# resonatev2.net
KiCad netlist of a schematic drawn in EAGLE
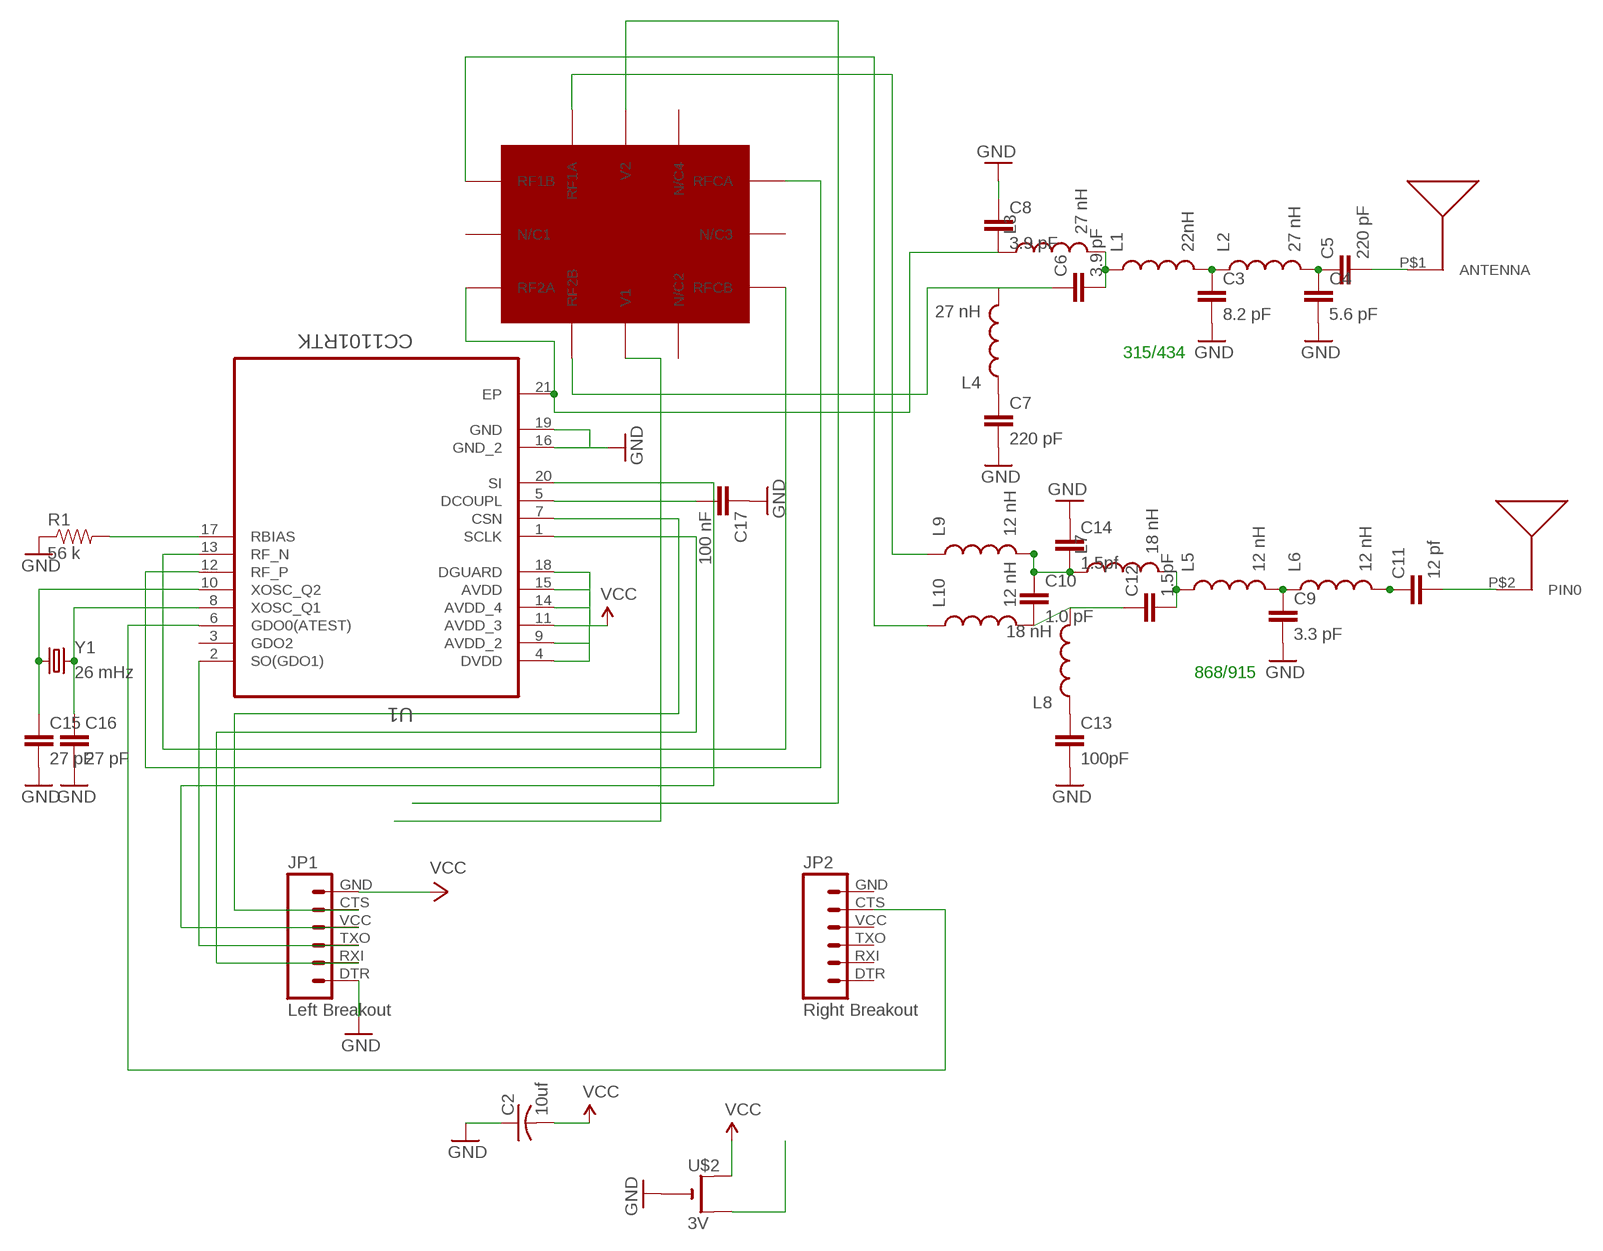
[diagram p0: schematic, sheet 1]

(export (version "E")
  (design (tool "Eeschema 10.0.6"))
  (components
    (comp (ref "C2")
      (value "10uf")
      (footprint "eagle-import:C0603")
      (libsource (lib "eagle-import") (part "C-USC0603"))
    )
    (comp (ref "C3")
      (value "8.2 pF")
      (footprint "eagle-import:0402-CAP")
      (libsource (lib "eagle-import") (part "CAP0402-CAP"))
    )
    (comp (ref "C4")
      (value "5.6 pF")
      (footprint "eagle-import:0402-CAP")
      (libsource (lib "eagle-import") (part "CAP0402-CAP"))
    )
    (comp (ref "C5")
      (value "220 pF")
      (footprint "eagle-import:0402-CAP")
      (libsource (lib "eagle-import") (part "CAP0402-CAP"))
    )
    (comp (ref "C6")
      (value "3.9 pF")
      (footprint "eagle-import:0402-CAP")
      (libsource (lib "eagle-import") (part "CAP0402-CAP"))
    )
    (comp (ref "C7")
      (value "220 pF")
      (footprint "eagle-import:0402-CAP")
      (libsource (lib "eagle-import") (part "CAP0402-CAP"))
    )
    (comp (ref "C8")
      (value "3.9 pF")
      (footprint "eagle-import:0402-CAP")
      (libsource (lib "eagle-import") (part "CAP0402-CAP"))
    )
    (comp (ref "C9")
      (value "3.3 pF")
      (footprint "eagle-import:0402-CAP")
      (libsource (lib "eagle-import") (part "CAP0402-CAP"))
    )
    (comp (ref "C10")
      (value "1.0 pF")
      (footprint "eagle-import:0402-CAP")
      (libsource (lib "eagle-import") (part "CAP0402-CAP"))
    )
    (comp (ref "C11")
      (value "12 pf")
      (footprint "eagle-import:0402-CAP")
      (libsource (lib "eagle-import") (part "CAP0402-CAP"))
    )
    (comp (ref "C12")
      (value "1.5pF")
      (footprint "eagle-import:0402-CAP")
      (libsource (lib "eagle-import") (part "CAP0402-CAP"))
    )
    (comp (ref "C13")
      (value "100pF")
      (footprint "eagle-import:0402-CAP")
      (libsource (lib "eagle-import") (part "CAP0402-CAP"))
    )
    (comp (ref "C14")
      (value "1.5pf")
      (footprint "eagle-import:0402-CAP")
      (libsource (lib "eagle-import") (part "CAP0402-CAP"))
    )
    (comp (ref "C15")
      (value "27 pF")
      (footprint "eagle-import:0402-CAP")
      (libsource (lib "eagle-import") (part "CAP0402-CAP"))
    )
    (comp (ref "C16")
      (value "27 pF")
      (footprint "eagle-import:0402-CAP")
      (libsource (lib "eagle-import") (part "CAP0402-CAP"))
    )
    (comp (ref "C17")
      (value "100 nF")
      (footprint "eagle-import:0402-CAP")
      (libsource (lib "eagle-import") (part "CAP0402-CAP"))
    )
    (comp (ref "JP1")
      (value "Left Breakout")
      (footprint "eagle-import:1X06")
      (libsource (lib "eagle-import") (part "M06SIP"))
    )
    (comp (ref "JP2")
      (value "Right Breakout")
      (footprint "eagle-import:1X06")
      (libsource (lib "eagle-import") (part "M06SIP"))
    )
    (comp (ref "L1")
      (value "22nH")
      (footprint "eagle-import:C0402")
      (libsource (lib "eagle-import") (part "INDUCTOR0402"))
    )
    (comp (ref "L2")
      (value "27 nH")
      (footprint "eagle-import:C0402")
      (libsource (lib "eagle-import") (part "INDUCTOR0402"))
    )
    (comp (ref "L3")
      (value "27 nH")
      (footprint "eagle-import:C0402")
      (libsource (lib "eagle-import") (part "INDUCTOR0402"))
    )
    (comp (ref "L4")
      (value "27 nH")
      (footprint "eagle-import:C0402")
      (libsource (lib "eagle-import") (part "INDUCTOR0402"))
    )
    (comp (ref "L5")
      (value "12 nH")
      (footprint "eagle-import:C0402")
      (libsource (lib "eagle-import") (part "INDUCTOR0402"))
    )
    (comp (ref "L6")
      (value "12 nH")
      (footprint "eagle-import:C0402")
      (libsource (lib "eagle-import") (part "INDUCTOR0402"))
    )
    (comp (ref "L7")
      (value "18 nH")
      (footprint "eagle-import:C0402")
      (libsource (lib "eagle-import") (part "INDUCTOR0402"))
    )
    (comp (ref "L8")
      (value "18 nH")
      (footprint "eagle-import:C0402")
      (libsource (lib "eagle-import") (part "INDUCTOR0402"))
    )
    (comp (ref "L9")
      (value "12 nH")
      (footprint "eagle-import:C0402")
      (libsource (lib "eagle-import") (part "INDUCTOR0402"))
    )
    (comp (ref "L10")
      (value "12 nH")
      (footprint "eagle-import:C0402")
      (libsource (lib "eagle-import") (part "INDUCTOR0402"))
    )
    (comp (ref "R1")
      (value "56 k")
      (footprint "eagle-import:0603-RES")
      (libsource (lib "eagle-import") (part "RESISTOR0603-RES"))
    )
    (comp (ref "U$2")
      (value "3V")
      (footprint "eagle-import:CR2032-THRU")
      (libsource (lib "eagle-import") (part "CR2032THM"))
    )
    (comp (ref "U$3")
      (value "ANT-868-JJB-ST")
      (footprint "eagle-import:ANT-868-JJB-ST")
      (libsource (lib "eagle-import") (part "ANT-868-JJB-ST"))
    )
    (comp (ref "U$5")
      (value "SKY13354-368LF")
      (footprint "eagle-import:SKY13354-368LF")
      (libsource (lib "eagle-import") (part "SKY13354-368LF"))
    )
    (comp (ref "U$6")
      (value "ANT1204F002R0433A")
      (footprint "eagle-import:ANT1204F002R0433A")
      (libsource (lib "eagle-import") (part "ANT1204F002R0433A"))
    )
    (comp (ref "U1")
      (value "CC1101RTK")
      (footprint "eagle-import:QFN50P400X400X90-21N")
      (libsource (lib "eagle-import") (part "CC1101RTK"))
    )
    (comp (ref "Y1")
      (value "26 mHz")
      (footprint "eagle-import:CRYSTAL-SMD-5X3")
      (libsource (lib "eagle-import") (part "CRYSTAL5X3"))
    )
  )
  (nets
    (net (code "1") (name "GND") (class "Default")
      (node (ref "C13") (pin "2") (pinfunction "2_2") (pintype "passive"))
      (node (ref "C14") (pin "1") (pinfunction "1_1") (pintype "passive"))
      (node (ref "C15") (pin "2") (pinfunction "2_2") (pintype "passive"))
      (node (ref "C16") (pin "2") (pinfunction "2_2") (pintype "passive"))
      (node (ref "C17") (pin "1") (pinfunction "1_1") (pintype "passive"))
      (node (ref "C2") (pin "1") (pinfunction "1_1") (pintype "passive"))
      (node (ref "C3") (pin "2") (pinfunction "2_2") (pintype "passive"))
      (node (ref "C4") (pin "2") (pinfunction "2_2") (pintype "passive"))
      (node (ref "C7") (pin "2") (pinfunction "2_2") (pintype "passive"))
      (node (ref "C8") (pin "1") (pinfunction "1_1") (pintype "passive"))
      (node (ref "C9") (pin "2") (pinfunction "2_2") (pintype "passive"))
      (node (ref "JP1") (pin "DTR") (pinfunction "1_DTR") (pintype "passive"))
      (node (ref "R1") (pin "1") (pinfunction "1_1") (pintype "passive"))
      (node (ref "U$2") (pin "-") (pinfunction "-_-") (pintype "passive"))
      (node (ref "U1") (pin "16") (pinfunction "GND_2_16") (pintype "passive"))
      (node (ref "U1") (pin "19") (pinfunction "GND_19") (pintype "passive"))
    )
    (net (code "2") (name "Net-(C3-Pad1)") (class "Default")
      (node (ref "C3") (pin "1") (pinfunction "1_1") (pintype "passive"))
      (node (ref "L1") (pin "2") (pinfunction "2_2") (pintype "passive"))
      (node (ref "L2") (pin "1") (pinfunction "1_1") (pintype "passive"))
    )
    (net (code "3") (name "Net-(C4-Pad1)") (class "Default")
      (node (ref "C4") (pin "1") (pinfunction "1_1") (pintype "passive"))
      (node (ref "C5") (pin "1") (pinfunction "1_1") (pintype "passive"))
      (node (ref "L2") (pin "2") (pinfunction "2_2") (pintype "passive"))
    )
    (net (code "4") (name "Net-(C6-Pad1)") (class "Default")
      (node (ref "C6") (pin "1") (pinfunction "1_1") (pintype "passive"))
      (node (ref "L4") (pin "2") (pinfunction "2_2") (pintype "passive"))
      (node (ref "U$5") (pin "RF2B") (pinfunction "RF2B_RF2B") (pintype "bidirectional"))
    )
    (net (code "5") (name "Net-(C6-Pad2)") (class "Default")
      (node (ref "C6") (pin "2") (pinfunction "2_2") (pintype "passive"))
      (node (ref "L1") (pin "1") (pinfunction "1_1") (pintype "passive"))
      (node (ref "L3") (pin "2") (pinfunction "2_2") (pintype "passive"))
    )
    (net (code "6") (name "Net-(C7-Pad1)") (class "Default")
      (node (ref "C7") (pin "1") (pinfunction "1_1") (pintype "passive"))
      (node (ref "L4") (pin "1") (pinfunction "1_1") (pintype "passive"))
    )
    (net (code "7") (name "Net-(C9-Pad1)") (class "Default")
      (node (ref "C9") (pin "1") (pinfunction "1_1") (pintype "passive"))
      (node (ref "L5") (pin "2") (pinfunction "2_2") (pintype "passive"))
      (node (ref "L6") (pin "1") (pinfunction "1_1") (pintype "passive"))
    )
    (net (code "8") (name "Net-(C10-Pad1)") (class "Default")
      (node (ref "C10") (pin "1") (pinfunction "1_1") (pintype "passive"))
      (node (ref "C14") (pin "2") (pinfunction "2_2") (pintype "passive"))
      (node (ref "L7") (pin "1") (pinfunction "1_1") (pintype "passive"))
      (node (ref "L9") (pin "2") (pinfunction "2_2") (pintype "passive"))
    )
    (net (code "9") (name "Net-(C10-Pad2)") (class "Default")
      (node (ref "C10") (pin "2") (pinfunction "2_2") (pintype "passive"))
      (node (ref "C12") (pin "1") (pinfunction "1_1") (pintype "passive"))
      (node (ref "L10") (pin "2") (pinfunction "2_2") (pintype "passive"))
      (node (ref "L8") (pin "2") (pinfunction "2_2") (pintype "passive"))
    )
    (net (code "10") (name "Net-(C11-Pad1)") (class "Default")
      (node (ref "C11") (pin "1") (pinfunction "1_1") (pintype "passive"))
      (node (ref "L6") (pin "2") (pinfunction "2_2") (pintype "passive"))
    )
    (net (code "11") (name "Net-(C12-Pad2)") (class "Default")
      (node (ref "C12") (pin "2") (pinfunction "2_2") (pintype "passive"))
      (node (ref "L5") (pin "1") (pinfunction "1_1") (pintype "passive"))
      (node (ref "L7") (pin "2") (pinfunction "2_2") (pintype "passive"))
    )
    (net (code "12") (name "Net-(C13-Pad1)") (class "Default")
      (node (ref "C13") (pin "1") (pinfunction "1_1") (pintype "passive"))
      (node (ref "L8") (pin "1") (pinfunction "1_1") (pintype "passive"))
    )
    (net (code "13") (name "Net-(JP1-2)") (class "Default")
      (node (ref "JP1") (pin "RXI") (pinfunction "2_RXI") (pintype "passive"))
      (node (ref "U1") (pin "1") (pinfunction "SCLK_1") (pintype "input"))
    )
    (net (code "14") (name "Net-(JP1-3)") (class "Default")
      (node (ref "JP1") (pin "TXO") (pinfunction "3_TXO") (pintype "passive"))
      (node (ref "U1") (pin "2") (pinfunction "SO(GDO1)_2") (pintype "output"))
    )
    (net (code "15") (name "Net-(JP1-4)") (class "Default")
      (node (ref "JP1") (pin "VCC") (pinfunction "4_VCC") (pintype "passive"))
      (node (ref "U1") (pin "20") (pinfunction "SI_20") (pintype "input"))
    )
    (net (code "16") (name "Net-(JP1-5)") (class "Default")
      (node (ref "JP1") (pin "CTS") (pinfunction "5_CTS") (pintype "passive"))
      (node (ref "U1") (pin "7") (pinfunction "CSN_7") (pintype "input"))
    )
    (net (code "17") (name "Net-(JP2-5)") (class "Default")
      (node (ref "JP2") (pin "CTS") (pinfunction "5_CTS") (pintype "passive"))
      (node (ref "U1") (pin "6") (pinfunction "GDO0(ATEST)_6") (pintype "bidirectional"))
    )
    (net (code "18") (name "Net-(L9-Pad1)") (class "Default")
      (node (ref "L9") (pin "1") (pinfunction "1_1") (pintype "passive"))
      (node (ref "U$5") (pin "RF1A") (pinfunction "RF1A_RF1A") (pintype "bidirectional"))
    )
    (net (code "19") (name "Net-(L10-Pad1)") (class "Default")
      (node (ref "L10") (pin "1") (pinfunction "1_1") (pintype "passive"))
      (node (ref "U$5") (pin "RF1B") (pinfunction "RF1B_RF1B") (pintype "bidirectional"))
    )
    (net (code "20") (name "Net-(U$3-PIN0)") (class "Default")
      (node (ref "C11") (pin "2") (pinfunction "2_2") (pintype "passive"))
      (node (ref "U$3") (pin "P$2") (pinfunction "PIN0_P$2") (pintype "input"))
    )
    (net (code "21") (name "Net-(U$6-ANTENNA)") (class "Default")
      (node (ref "C5") (pin "2") (pinfunction "2_2") (pintype "passive"))
      (node (ref "U$6") (pin "P$1") (pinfunction "ANTENNA_P$1") (pintype "input"))
    )
    (net (code "22") (name "Net-(U1-DCOUPL)") (class "Default")
      (node (ref "C17") (pin "2") (pinfunction "2_2") (pintype "passive"))
      (node (ref "U1") (pin "5") (pinfunction "DCOUPL_5") (pintype "power_in"))
    )
    (net (code "23") (name "Net-(U1-EP)") (class "Default")
      (node (ref "C8") (pin "2") (pinfunction "2_2") (pintype "passive"))
      (node (ref "L3") (pin "1") (pinfunction "1_1") (pintype "passive"))
      (node (ref "U$5") (pin "RF2A") (pinfunction "RF2A_RF2A") (pintype "bidirectional"))
      (node (ref "U1") (pin "21") (pinfunction "EP_21") (pintype "passive"))
    )
    (net (code "24") (name "Net-(U1-RBIAS)") (class "Default")
      (node (ref "R1") (pin "2") (pinfunction "2_2") (pintype "passive"))
      (node (ref "U1") (pin "17") (pinfunction "RBIAS_17") (pintype "bidirectional"))
    )
    (net (code "25") (name "Net-(U1-RF_N)") (class "Default")
      (node (ref "U$5") (pin "RFCB") (pinfunction "RFCB_RFCB") (pintype "bidirectional"))
      (node (ref "U1") (pin "13") (pinfunction "RF_N_13") (pintype "bidirectional"))
    )
    (net (code "26") (name "Net-(U1-RF_P)") (class "Default")
      (node (ref "U$5") (pin "RFCA") (pinfunction "RFCA_RFCA") (pintype "bidirectional"))
      (node (ref "U1") (pin "12") (pinfunction "RF_P_12") (pintype "bidirectional"))
    )
    (net (code "27") (name "Net-(U1-XOSC_Q1)") (class "Default")
      (node (ref "C16") (pin "1") (pinfunction "1_1") (pintype "passive"))
      (node (ref "U1") (pin "8") (pinfunction "XOSC_Q1_8") (pintype "bidirectional"))
      (node (ref "Y1") (pin "3") (pinfunction "2_3") (pintype "passive"))
    )
    (net (code "28") (name "Net-(U1-XOSC_Q2)") (class "Default")
      (node (ref "C15") (pin "1") (pinfunction "1_1") (pintype "passive"))
      (node (ref "U1") (pin "10") (pinfunction "XOSC_Q2_10") (pintype "bidirectional"))
      (node (ref "Y1") (pin "1") (pinfunction "1_1") (pintype "passive"))
    )
    (net (code "29") (name "VCC") (class "Default")
      (node (ref "C2") (pin "2") (pinfunction "2_2") (pintype "passive"))
      (node (ref "JP1") (pin "GND") (pinfunction "6_GND") (pintype "passive"))
      (node (ref "U$2") (pin "+1") (pinfunction "+_+1") (pintype "passive"))
      (node (ref "U1") (pin "11") (pinfunction "AVDD_3_11") (pintype "power_in"))
      (node (ref "U1") (pin "14") (pinfunction "AVDD_4_14") (pintype "power_in"))
      (node (ref "U1") (pin "15") (pinfunction "AVDD_15") (pintype "power_in"))
      (node (ref "U1") (pin "18") (pinfunction "DGUARD_18") (pintype "power_in"))
      (node (ref "U1") (pin "4") (pinfunction "DVDD_4") (pintype "power_in"))
      (node (ref "U1") (pin "9") (pinfunction "AVDD_2_9") (pintype "power_in"))
    )
    (net (code "30") (name "unconnected-(JP2-1-PadDTR)") (class "Default")
      (node (ref "JP2") (pin "DTR") (pinfunction "1_DTR") (pintype "passive"))
    )
    (net (code "31") (name "unconnected-(JP2-2-PadRXI)") (class "Default")
      (node (ref "JP2") (pin "RXI") (pinfunction "2_RXI") (pintype "passive"))
    )
    (net (code "32") (name "unconnected-(JP2-3-PadTXO)") (class "Default")
      (node (ref "JP2") (pin "TXO") (pinfunction "3_TXO") (pintype "passive"))
    )
    (net (code "33") (name "unconnected-(JP2-4-PadVCC)") (class "Default")
      (node (ref "JP2") (pin "VCC") (pinfunction "4_VCC") (pintype "passive"))
    )
    (net (code "34") (name "unconnected-(JP2-6-PadGND)") (class "Default")
      (node (ref "JP2") (pin "GND") (pinfunction "6_GND") (pintype "passive"))
    )
    (net (code "35") (name "unconnected-(U$2-+1-Pad+2)") (class "Default")
      (node (ref "U$2") (pin "+2") (pinfunction "+1_+2") (pintype "passive"))
    )
    (net (code "36") (name "unconnected-(U$5-N{slash}C1-PadN{slash}C)") (class "Default")
      (node (ref "U$5") (pin "N/C") (pinfunction "N/C1_N/C") (pintype "no_connect"))
    )
    (net (code "37") (name "unconnected-(U$5-PadN{slash}C2)") (class "Default")
      (node (ref "U$5") (pin "N/C2") (pinfunction "N/C2_N/C2") (pintype "bidirectional"))
    )
    (net (code "38") (name "unconnected-(U$5-PadN{slash}C3)") (class "Default")
      (node (ref "U$5") (pin "N/C3") (pinfunction "N/C3_N/C3") (pintype "no_connect"))
    )
    (net (code "39") (name "unconnected-(U$5-PadN{slash}C4)") (class "Default")
      (node (ref "U$5") (pin "N/C4") (pinfunction "N/C4_N/C4") (pintype "no_connect"))
    )
    (net (code "40") (name "unconnected-(U$5-PadV1)") (class "Default")
      (node (ref "U$5") (pin "V1") (pinfunction "V1_V1") (pintype "input"))
    )
    (net (code "41") (name "unconnected-(U$5-PadV2)") (class "Default")
      (node (ref "U$5") (pin "V2") (pinfunction "V2_V2") (pintype "input"))
    )
    (net (code "42") (name "unconnected-(U1-GDO2-Pad3)") (class "Default")
      (node (ref "U1") (pin "3") (pinfunction "GDO2_3") (pintype "output"))
    )
  )
)
